# lna-plug.net
KiCad netlist of a schematic drawn in EAGLE
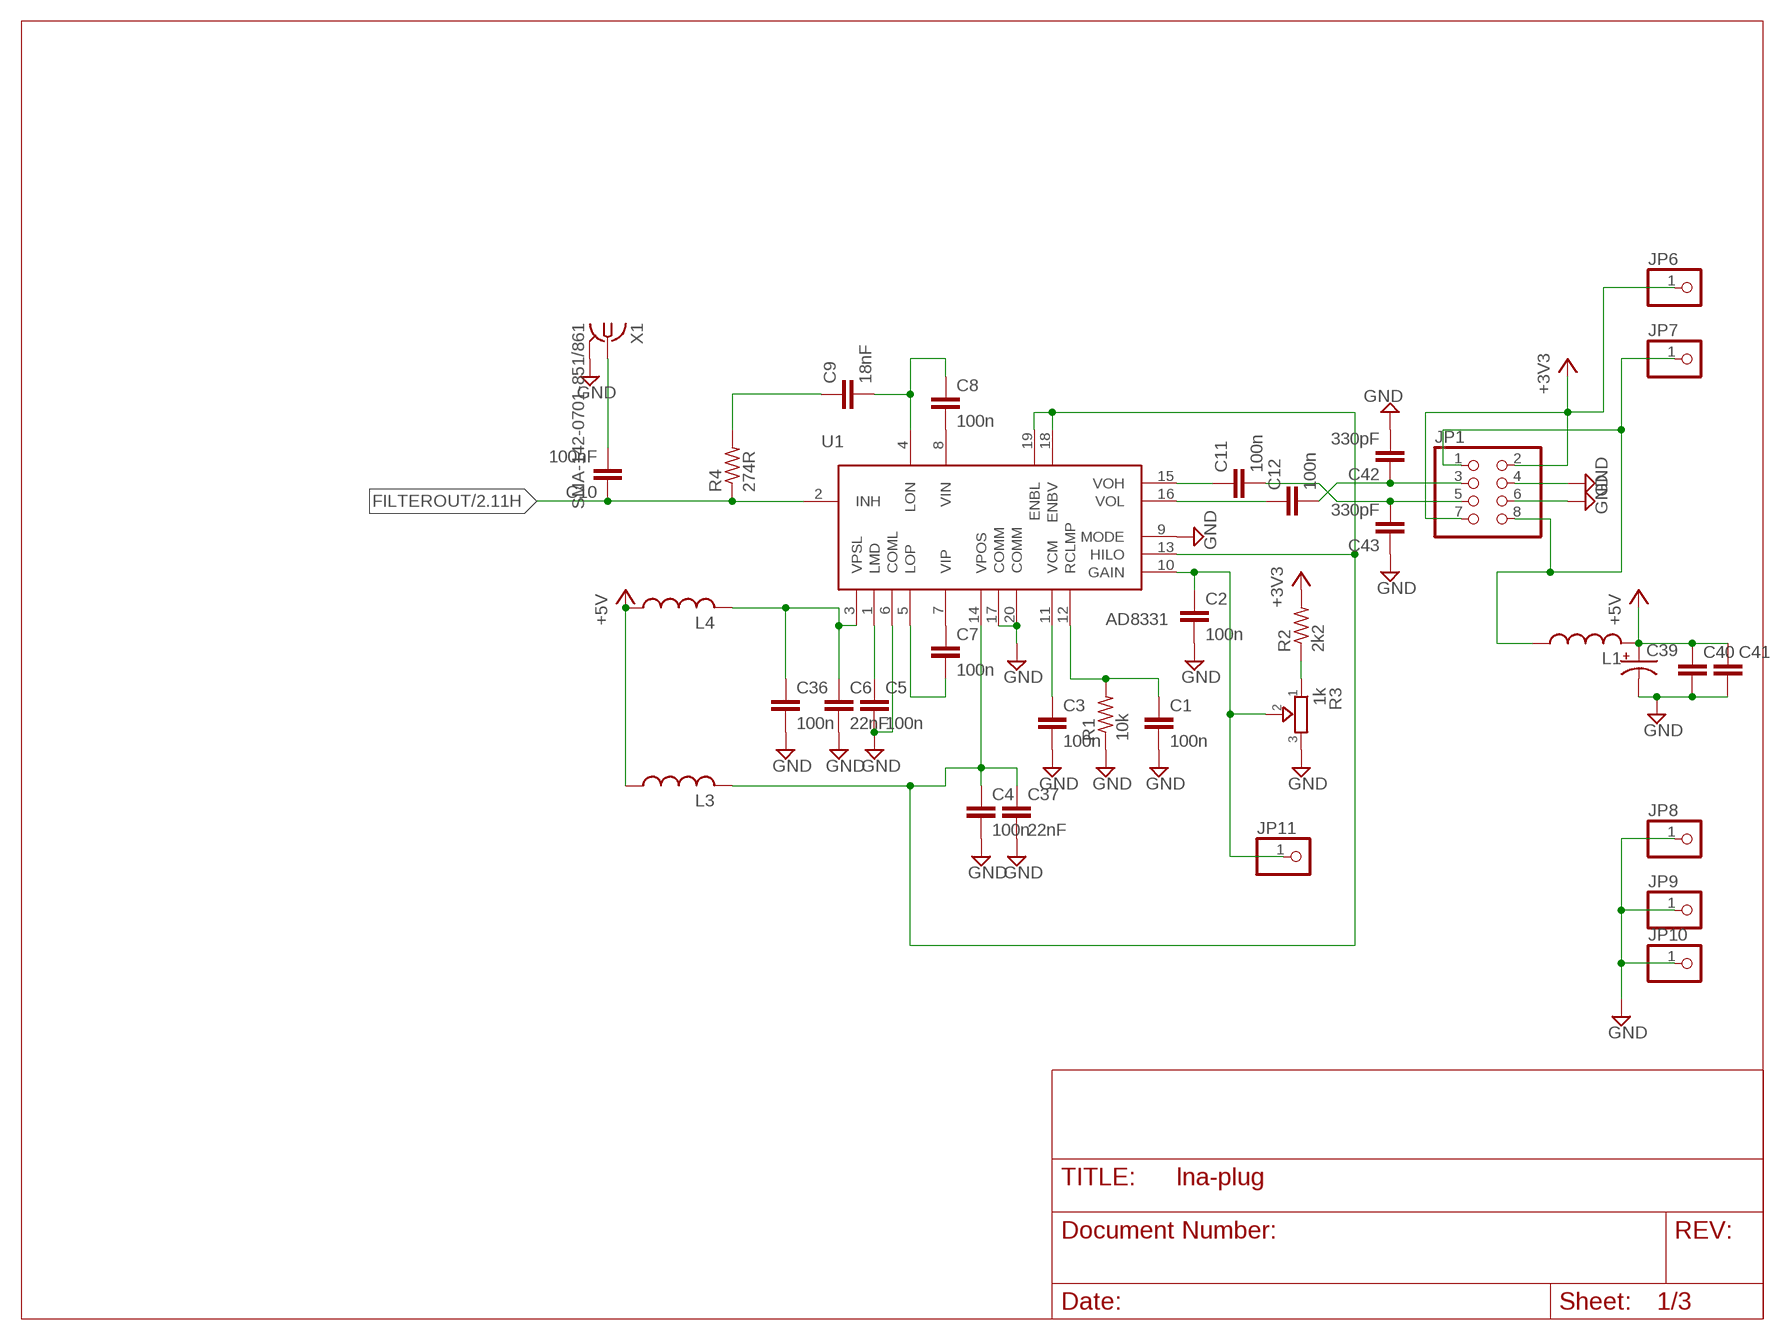
[diagram p0: schematic, sheet 1]
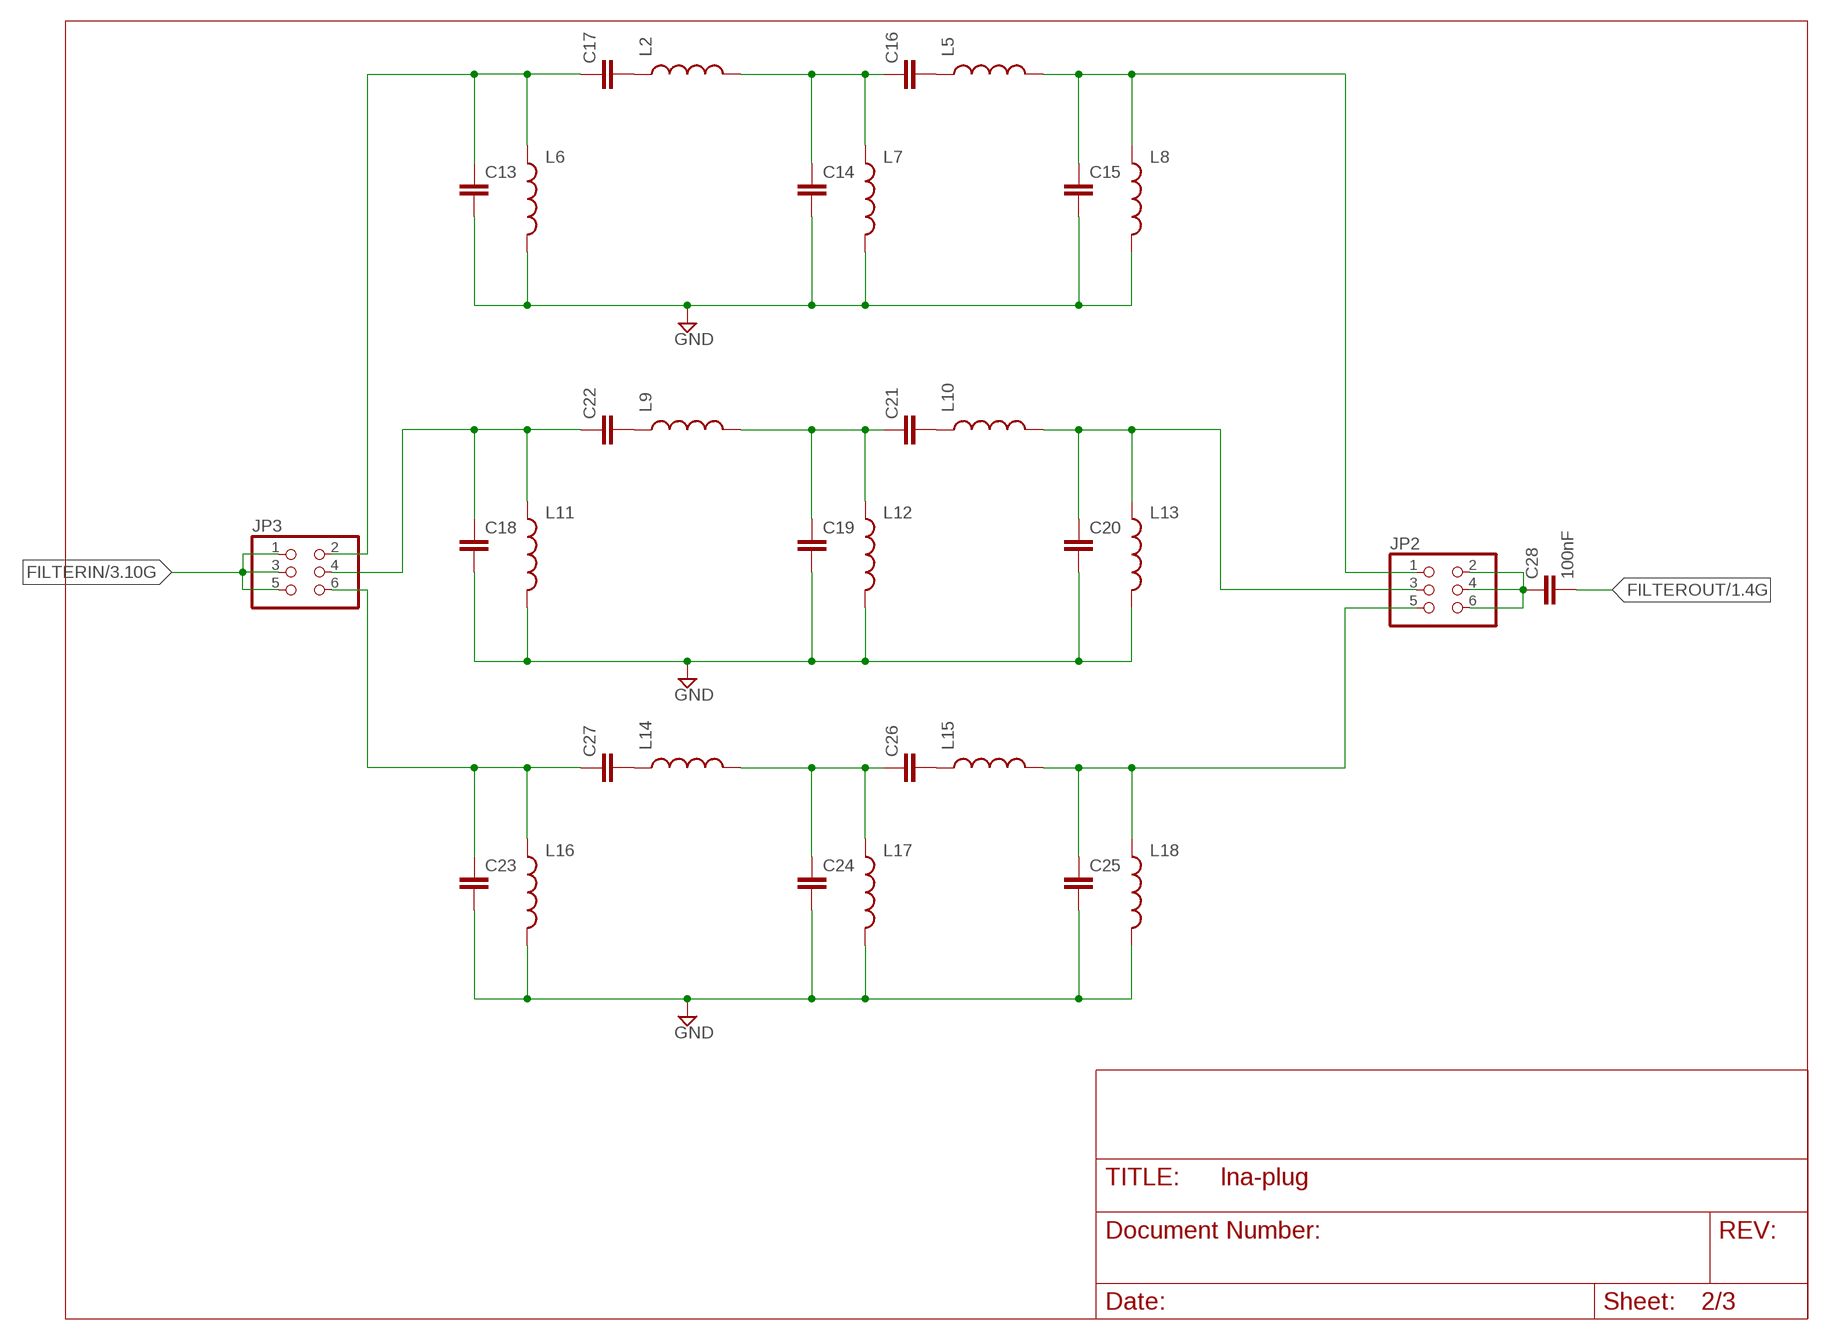
[diagram p1: schematic, sheet 2]
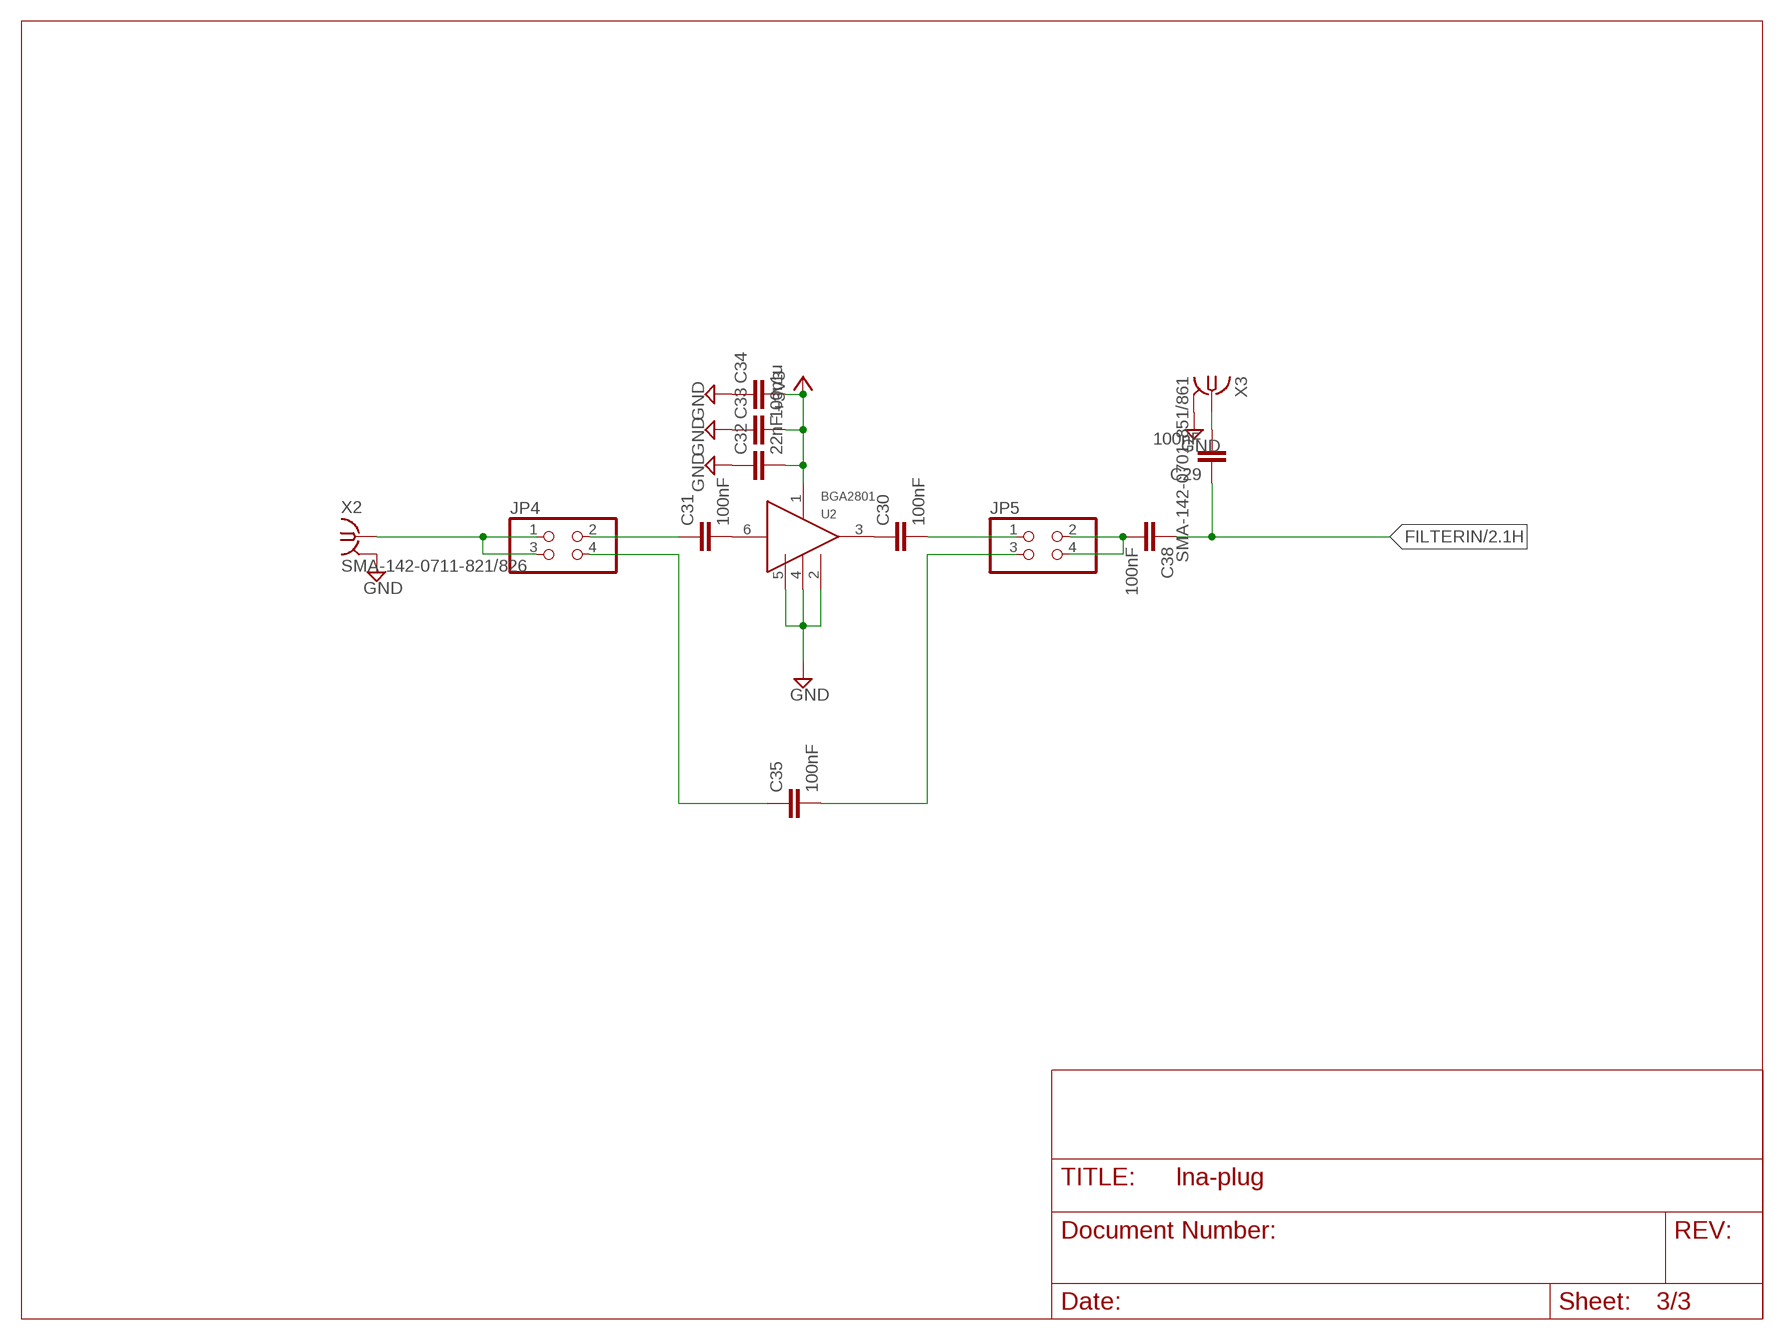
[diagram p2: schematic, sheet 3]

(export (version "E")
  (design (tool "Eeschema 10.0.6"))
  (components
    (comp (ref "C13")
      (value "C-EUC0603")
      (footprint "eagle-import:C0603")
      (libsource (lib "eagle-import") (part "resistor_C-EUC0603"))
    )
    (comp (ref "C14")
      (value "C-EUC0603")
      (footprint "eagle-import:C0603")
      (libsource (lib "eagle-import") (part "resistor_C-EUC0603"))
    )
    (comp (ref "C15")
      (value "C-EUC0603")
      (footprint "eagle-import:C0603")
      (libsource (lib "eagle-import") (part "resistor_C-EUC0603"))
    )
    (comp (ref "C16")
      (value "C-EUC0603")
      (footprint "eagle-import:C0603")
      (libsource (lib "eagle-import") (part "resistor_C-EUC0603"))
    )
    (comp (ref "C17")
      (value "C-EUC0603")
      (footprint "eagle-import:C0603")
      (libsource (lib "eagle-import") (part "resistor_C-EUC0603"))
    )
    (comp (ref "C18")
      (value "C-EUC0603")
      (footprint "eagle-import:C0603")
      (libsource (lib "eagle-import") (part "resistor_C-EUC0603"))
    )
    (comp (ref "C19")
      (value "C-EUC0603")
      (footprint "eagle-import:C0603")
      (libsource (lib "eagle-import") (part "resistor_C-EUC0603"))
    )
    (comp (ref "C20")
      (value "C-EUC0603")
      (footprint "eagle-import:C0603")
      (libsource (lib "eagle-import") (part "resistor_C-EUC0603"))
    )
    (comp (ref "C21")
      (value "C-EUC0603")
      (footprint "eagle-import:C0603")
      (libsource (lib "eagle-import") (part "resistor_C-EUC0603"))
    )
    (comp (ref "C22")
      (value "C-EUC0603")
      (footprint "eagle-import:C0603")
      (libsource (lib "eagle-import") (part "resistor_C-EUC0603"))
    )
    (comp (ref "C23")
      (value "C-EUC0603")
      (footprint "eagle-import:C0603")
      (libsource (lib "eagle-import") (part "resistor_C-EUC0603"))
    )
    (comp (ref "C24")
      (value "C-EUC0603")
      (footprint "eagle-import:C0603")
      (libsource (lib "eagle-import") (part "resistor_C-EUC0603"))
    )
    (comp (ref "C25")
      (value "C-EUC0603")
      (footprint "eagle-import:C0603")
      (libsource (lib "eagle-import") (part "resistor_C-EUC0603"))
    )
    (comp (ref "C26")
      (value "C-EUC0603")
      (footprint "eagle-import:C0603")
      (libsource (lib "eagle-import") (part "resistor_C-EUC0603"))
    )
    (comp (ref "C27")
      (value "C-EUC0603")
      (footprint "eagle-import:C0603")
      (libsource (lib "eagle-import") (part "resistor_C-EUC0603"))
    )
    (comp (ref "C28")
      (value "100nF")
      (footprint "eagle-import:C0603")
      (libsource (lib "eagle-import") (part "resistor_C-EUC0603"))
    )
    (comp (ref "JP2")
      (value "PINHD-2X3")
      (footprint "eagle-import:2X03")
      (libsource (lib "eagle-import") (part "PINHD-2X3"))
    )
    (comp (ref "JP3")
      (value "PINHD-2X3")
      (footprint "eagle-import:2X03")
      (libsource (lib "eagle-import") (part "PINHD-2X3"))
    )
    (comp (ref "L2")
      (value "INDUCTOR0603")
      (footprint "eagle-import:0603")
      (libsource (lib "eagle-import") (part "INDUCTOR0603"))
    )
    (comp (ref "L5")
      (value "INDUCTOR0603")
      (footprint "eagle-import:0603")
      (libsource (lib "eagle-import") (part "INDUCTOR0603"))
    )
    (comp (ref "L6")
      (value "INDUCTOR0603")
      (footprint "eagle-import:0603")
      (libsource (lib "eagle-import") (part "INDUCTOR0603"))
    )
    (comp (ref "L7")
      (value "INDUCTOR0603")
      (footprint "eagle-import:0603")
      (libsource (lib "eagle-import") (part "INDUCTOR0603"))
    )
    (comp (ref "L8")
      (value "INDUCTOR0603")
      (footprint "eagle-import:0603")
      (libsource (lib "eagle-import") (part "INDUCTOR0603"))
    )
    (comp (ref "L9")
      (value "INDUCTOR0603")
      (footprint "eagle-import:0603")
      (libsource (lib "eagle-import") (part "INDUCTOR0603"))
    )
    (comp (ref "L10")
      (value "INDUCTOR0603")
      (footprint "eagle-import:0603")
      (libsource (lib "eagle-import") (part "INDUCTOR0603"))
    )
    (comp (ref "L11")
      (value "INDUCTOR0603")
      (footprint "eagle-import:0603")
      (libsource (lib "eagle-import") (part "INDUCTOR0603"))
    )
    (comp (ref "L12")
      (value "INDUCTOR0603")
      (footprint "eagle-import:0603")
      (libsource (lib "eagle-import") (part "INDUCTOR0603"))
    )
    (comp (ref "L13")
      (value "INDUCTOR0603")
      (footprint "eagle-import:0603")
      (libsource (lib "eagle-import") (part "INDUCTOR0603"))
    )
    (comp (ref "L14")
      (value "INDUCTOR0603")
      (footprint "eagle-import:0603")
      (libsource (lib "eagle-import") (part "INDUCTOR0603"))
    )
    (comp (ref "L15")
      (value "INDUCTOR0603")
      (footprint "eagle-import:0603")
      (libsource (lib "eagle-import") (part "INDUCTOR0603"))
    )
    (comp (ref "L16")
      (value "INDUCTOR0603")
      (footprint "eagle-import:0603")
      (libsource (lib "eagle-import") (part "INDUCTOR0603"))
    )
    (comp (ref "L17")
      (value "INDUCTOR0603")
      (footprint "eagle-import:0603")
      (libsource (lib "eagle-import") (part "INDUCTOR0603"))
    )
    (comp (ref "L18")
      (value "INDUCTOR0603")
      (footprint "eagle-import:0603")
      (libsource (lib "eagle-import") (part "INDUCTOR0603"))
    )
    (comp (ref "C1")
      (value "100n")
      (footprint "eagle-import:C0603")
      (libsource (lib "eagle-import") (part "resistor_C-EUC0603"))
    )
    (comp (ref "C2")
      (value "100n")
      (footprint "eagle-import:C0603")
      (libsource (lib "eagle-import") (part "resistor_C-EUC0603"))
    )
    (comp (ref "C3")
      (value "100n")
      (footprint "eagle-import:C0603")
      (libsource (lib "eagle-import") (part "resistor_C-EUC0603"))
    )
    (comp (ref "C4")
      (value "100n")
      (footprint "eagle-import:C0603")
      (libsource (lib "eagle-import") (part "resistor_C-EUC0603"))
    )
    (comp (ref "C5")
      (value "100n")
      (footprint "eagle-import:C0603")
      (libsource (lib "eagle-import") (part "resistor_C-EUC0603"))
    )
    (comp (ref "C6")
      (value "22nF")
      (footprint "eagle-import:C0603")
      (libsource (lib "eagle-import") (part "resistor_C-EUC0603"))
    )
    (comp (ref "C7")
      (value "100n")
      (footprint "eagle-import:C0603")
      (libsource (lib "eagle-import") (part "resistor_C-EUC0603"))
    )
    (comp (ref "C8")
      (value "100n")
      (footprint "eagle-import:C0603")
      (libsource (lib "eagle-import") (part "resistor_C-EUC0603"))
    )
    (comp (ref "C9")
      (value "18nF")
      (footprint "eagle-import:C0603")
      (libsource (lib "eagle-import") (part "resistor_C-EUC0603"))
    )
    (comp (ref "C10")
      (value "100nF")
      (footprint "eagle-import:C0603")
      (libsource (lib "eagle-import") (part "resistor_C-EUC0603"))
    )
    (comp (ref "C11")
      (value "100n")
      (footprint "eagle-import:C0603")
      (libsource (lib "eagle-import") (part "resistor_C-EUC0603"))
    )
    (comp (ref "C12")
      (value "100n")
      (footprint "eagle-import:C0603")
      (libsource (lib "eagle-import") (part "resistor_C-EUC0603"))
    )
    (comp (ref "C36")
      (value "100n")
      (footprint "eagle-import:C0603")
      (libsource (lib "eagle-import") (part "resistor_C-EUC0603"))
    )
    (comp (ref "C37")
      (value "22nF")
      (footprint "eagle-import:C0603")
      (libsource (lib "eagle-import") (part "resistor_C-EUC0603"))
    )
    (comp (ref "C39")
      (value "CPOL-USSMCC")
      (footprint "eagle-import:SMC_C")
      (libsource (lib "eagle-import") (part "CPOL-USSMCC"))
    )
    (comp (ref "C40")
      (value "C-EUC1206")
      (footprint "eagle-import:C1206")
      (libsource (lib "eagle-import") (part "C-EUC1206"))
    )
    (comp (ref "C41")
      (value "C-EUC0805")
      (footprint "eagle-import:C0805")
      (libsource (lib "eagle-import") (part "C-EUC0805"))
    )
    (comp (ref "C42")
      (value "330pF")
      (footprint "eagle-import:C0603")
      (libsource (lib "eagle-import") (part "resistor_C-EUC0603"))
    )
    (comp (ref "C43")
      (value "330pF")
      (footprint "eagle-import:C0603")
      (libsource (lib "eagle-import") (part "resistor_C-EUC0603"))
    )
    (comp (ref "JP1")
      (value "PINHD-2X4")
      (footprint "eagle-import:2X04")
      (libsource (lib "eagle-import") (part "PINHD-2X4"))
    )
    (comp (ref "JP6")
      (value "PINHD-1X1")
      (footprint "eagle-import:1X01")
      (libsource (lib "eagle-import") (part "PINHD-1X1"))
    )
    (comp (ref "JP7")
      (value "PINHD-1X1")
      (footprint "eagle-import:1X01")
      (libsource (lib "eagle-import") (part "PINHD-1X1"))
    )
    (comp (ref "JP8")
      (value "PINHD-1X1")
      (footprint "eagle-import:1X01")
      (libsource (lib "eagle-import") (part "PINHD-1X1"))
    )
    (comp (ref "JP9")
      (value "PINHD-1X1")
      (footprint "eagle-import:1X01")
      (libsource (lib "eagle-import") (part "PINHD-1X1"))
    )
    (comp (ref "JP10")
      (value "PINHD-1X1")
      (footprint "eagle-import:1X01")
      (libsource (lib "eagle-import") (part "PINHD-1X1"))
    )
    (comp (ref "JP11")
      (value "PINHD-1X1")
      (footprint "eagle-import:1X01")
      (libsource (lib "eagle-import") (part "PINHD-1X1"))
    )
    (comp (ref "L1")
      (value "L-USL2012C")
      (footprint "eagle-import:L2012C")
      (libsource (lib "eagle-import") (part "L-USL2012C"))
    )
    (comp (ref "L3")
      (value "L-USL2012C")
      (footprint "eagle-import:L2012C")
      (libsource (lib "eagle-import") (part "L-USL2012C"))
    )
    (comp (ref "L4")
      (value "L-USL2012C")
      (footprint "eagle-import:L2012C")
      (libsource (lib "eagle-import") (part "L-USL2012C"))
    )
    (comp (ref "R1")
      (value "10k")
      (footprint "eagle-import:R0603")
      (libsource (lib "eagle-import") (part "R-US_R0603"))
    )
    (comp (ref "R2")
      (value "2k2")
      (footprint "eagle-import:R0603")
      (libsource (lib "eagle-import") (part "R-US_R0603"))
    )
    (comp (ref "R3")
      (value "1k")
      (footprint "eagle-import:TRIMMER_3362P")
      (libsource (lib "eagle-import") (part "TRIMMER-3362P"))
    )
    (comp (ref "R4")
      (value "274R")
      (footprint "eagle-import:R0603")
      (libsource (lib "eagle-import") (part "R-US_R0603"))
    )
    (comp (ref "U1")
      (value "AD8331")
      (footprint "eagle-import:QSOP20")
      (libsource (lib "eagle-import") (part "AD8331"))
    )
    (comp (ref "X1")
      (value "SMA-142-0701-851/861")
      (footprint "eagle-import:J502-ND-142-0701-851_861")
      (fields (field (name "MF") "JOHNSON COMPONENTS") (field (name "MPN") "142-0701-851"))
      (libsource (lib "eagle-import") (part "SMA-142-0701-851/861"))
    )
    (comp (ref "C29")
      (value "100nF")
      (footprint "eagle-import:C0603")
      (libsource (lib "eagle-import") (part "resistor_C-EUC0603"))
    )
    (comp (ref "C30")
      (value "100nF")
      (footprint "eagle-import:C0603")
      (libsource (lib "eagle-import") (part "resistor_C-EUC0603"))
    )
    (comp (ref "C31")
      (value "100nF")
      (footprint "eagle-import:C0603")
      (libsource (lib "eagle-import") (part "resistor_C-EUC0603"))
    )
    (comp (ref "C32")
      (value "22nF")
      (footprint "eagle-import:C0603")
      (libsource (lib "eagle-import") (part "resistor_C-EUC0603"))
    )
    (comp (ref "C33")
      (value "100n")
      (footprint "eagle-import:C0603")
      (libsource (lib "eagle-import") (part "resistor_C-EUC0603"))
    )
    (comp (ref "C34")
      (value "1u")
      (footprint "eagle-import:C0603")
      (libsource (lib "eagle-import") (part "resistor_C-EUC0603"))
    )
    (comp (ref "C35")
      (value "100nF")
      (footprint "eagle-import:C0603")
      (libsource (lib "eagle-import") (part "resistor_C-EUC0603"))
    )
    (comp (ref "C38")
      (value "100nF")
      (footprint "eagle-import:C0603")
      (libsource (lib "eagle-import") (part "resistor_C-EUC0603"))
    )
    (comp (ref "JP4")
      (value "PINHD-2X2")
      (footprint "eagle-import:2X02")
      (libsource (lib "eagle-import") (part "PINHD-2X2"))
    )
    (comp (ref "JP5")
      (value "PINHD-2X2")
      (footprint "eagle-import:2X02")
      (libsource (lib "eagle-import") (part "PINHD-2X2"))
    )
    (comp (ref "U2")
      (value "BGA2801")
      (footprint "eagle-import:SOTT323-6")
      (libsource (lib "eagle-import") (part "BGA2801"))
    )
    (comp (ref "X2")
      (value "SMA-142-0711-821/826")
      (footprint "eagle-import:J502-ND-142-0711-821_826")
      (fields (field (name "MF") "JOHNSON COMPONENTS") (field (name "MPN") "142-0711-821"))
      (libsource (lib "eagle-import") (part "SMA-142-0711-821/826"))
    )
    (comp (ref "X3")
      (value "SMA-142-0701-851/861")
      (footprint "eagle-import:J502-ND-142-0701-851_861")
      (fields (field (name "MF") "JOHNSON COMPONENTS") (field (name "MPN") "142-0701-851"))
      (libsource (lib "eagle-import") (part "SMA-142-0701-851/861"))
    )
  )
  (nets
    (net (code "1") (name "+3V3") (class "Default")
      (node (ref "C32") (pin "2") (pinfunction "2_2") (pintype "passive"))
      (node (ref "C33") (pin "2") (pinfunction "2_2") (pintype "passive"))
      (node (ref "C34") (pin "2") (pinfunction "2_2") (pintype "passive"))
      (node (ref "JP1") (pin "2") (pinfunction "2_2") (pintype "passive"))
      (node (ref "JP1") (pin "7") (pinfunction "7_7") (pintype "passive"))
      (node (ref "JP6") (pin "1") (pinfunction "1_1") (pintype "passive"))
      (node (ref "R2") (pin "2") (pinfunction "2_2") (pintype "passive"))
      (node (ref "U2") (pin "1") (pinfunction "VCC_1") (pintype "bidirectional"))
    )
    (net (code "2") (name "+5V") (class "Default")
      (node (ref "C39") (pin "+") (pinfunction "+_+") (pintype "passive"))
      (node (ref "C40") (pin "1") (pinfunction "1_1") (pintype "passive"))
      (node (ref "C41") (pin "1") (pinfunction "1_1") (pintype "passive"))
      (node (ref "L1") (pin "2") (pinfunction "2_2") (pintype "passive"))
      (node (ref "L3") (pin "1") (pinfunction "1_1") (pintype "passive"))
      (node (ref "L4") (pin "1") (pinfunction "1_1") (pintype "passive"))
    )
    (net (code "3") (name "FILTERIN") (class "Default")
      (node (ref "C29") (pin "1") (pinfunction "1_1") (pintype "passive"))
      (node (ref "C38") (pin "1") (pinfunction "1_1") (pintype "passive"))
      (node (ref "JP3") (pin "1") (pinfunction "1_1") (pintype "passive"))
      (node (ref "JP3") (pin "3") (pinfunction "3_3") (pintype "passive"))
      (node (ref "JP3") (pin "5") (pinfunction "5_5") (pintype "passive"))
    )
    (net (code "4") (name "FILTEROUT") (class "Default")
      (node (ref "C10") (pin "1") (pinfunction "1_1") (pintype "passive"))
      (node (ref "C28") (pin "2") (pinfunction "2_2") (pintype "passive"))
      (node (ref "R4") (pin "1") (pinfunction "1_1") (pintype "passive"))
      (node (ref "U1") (pin "2") (pinfunction "INH_2") (pintype "bidirectional"))
    )
    (net (code "5") (name "GND") (class "Default")
      (node (ref "C1") (pin "2") (pinfunction "2_2") (pintype "passive"))
      (node (ref "C13") (pin "2") (pinfunction "2_2") (pintype "passive"))
      (node (ref "C14") (pin "2") (pinfunction "2_2") (pintype "passive"))
      (node (ref "C15") (pin "2") (pinfunction "2_2") (pintype "passive"))
      (node (ref "C18") (pin "2") (pinfunction "2_2") (pintype "passive"))
      (node (ref "C19") (pin "2") (pinfunction "2_2") (pintype "passive"))
      (node (ref "C2") (pin "2") (pinfunction "2_2") (pintype "passive"))
      (node (ref "C20") (pin "2") (pinfunction "2_2") (pintype "passive"))
      (node (ref "C23") (pin "2") (pinfunction "2_2") (pintype "passive"))
      (node (ref "C24") (pin "2") (pinfunction "2_2") (pintype "passive"))
      (node (ref "C25") (pin "2") (pinfunction "2_2") (pintype "passive"))
      (node (ref "C3") (pin "2") (pinfunction "2_2") (pintype "passive"))
      (node (ref "C32") (pin "1") (pinfunction "1_1") (pintype "passive"))
      (node (ref "C33") (pin "1") (pinfunction "1_1") (pintype "passive"))
      (node (ref "C34") (pin "1") (pinfunction "1_1") (pintype "passive"))
      (node (ref "C36") (pin "2") (pinfunction "2_2") (pintype "passive"))
      (node (ref "C37") (pin "2") (pinfunction "2_2") (pintype "passive"))
      (node (ref "C39") (pin "-") (pinfunction "-_-") (pintype "passive"))
      (node (ref "C4") (pin "2") (pinfunction "2_2") (pintype "passive"))
      (node (ref "C40") (pin "2") (pinfunction "2_2") (pintype "passive"))
      (node (ref "C41") (pin "2") (pinfunction "2_2") (pintype "passive"))
      (node (ref "C42") (pin "2") (pinfunction "2_2") (pintype "passive"))
      (node (ref "C43") (pin "1") (pinfunction "1_1") (pintype "passive"))
      (node (ref "C5") (pin "2") (pinfunction "2_2") (pintype "passive"))
      (node (ref "C6") (pin "2") (pinfunction "2_2") (pintype "passive"))
      (node (ref "JP1") (pin "4") (pinfunction "4_4") (pintype "passive"))
      (node (ref "JP1") (pin "6") (pinfunction "6_6") (pintype "passive"))
      (node (ref "JP10") (pin "1") (pinfunction "1_1") (pintype "passive"))
      (node (ref "JP8") (pin "1") (pinfunction "1_1") (pintype "passive"))
      (node (ref "JP9") (pin "1") (pinfunction "1_1") (pintype "passive"))
      (node (ref "L11") (pin "2") (pinfunction "2_2") (pintype "passive"))
      (node (ref "L12") (pin "2") (pinfunction "2_2") (pintype "passive"))
      (node (ref "L13") (pin "2") (pinfunction "2_2") (pintype "passive"))
      (node (ref "L16") (pin "2") (pinfunction "2_2") (pintype "passive"))
      (node (ref "L17") (pin "2") (pinfunction "2_2") (pintype "passive"))
      (node (ref "L18") (pin "2") (pinfunction "2_2") (pintype "passive"))
      (node (ref "L6") (pin "2") (pinfunction "2_2") (pintype "passive"))
      (node (ref "L7") (pin "2") (pinfunction "2_2") (pintype "passive"))
      (node (ref "L8") (pin "2") (pinfunction "2_2") (pintype "passive"))
      (node (ref "R1") (pin "1") (pinfunction "1_1") (pintype "passive"))
      (node (ref "R3") (pin "3") (pinfunction "3_3") (pintype "passive"))
      (node (ref "U1") (pin "17") (pinfunction "COMM_17") (pintype "bidirectional"))
      (node (ref "U1") (pin "20") (pinfunction "COMM_20") (pintype "bidirectional"))
      (node (ref "U1") (pin "6") (pinfunction "COML_6") (pintype "bidirectional"))
      (node (ref "U1") (pin "9") (pinfunction "MODE_9") (pintype "bidirectional"))
      (node (ref "U2") (pin "2") (pinfunction "GND_2") (pintype "bidirectional"))
      (node (ref "U2") (pin "4") (pinfunction "GND_4") (pintype "bidirectional"))
      (node (ref "U2") (pin "5") (pinfunction "GND_5") (pintype "bidirectional"))
      (node (ref "X1") (pin "G@1") (pinfunction "2_G@1") (pintype "passive"))
      (node (ref "X1") (pin "G@2") (pinfunction "2_G@2") (pintype "passive"))
      (node (ref "X1") (pin "G@3") (pinfunction "2_G@3") (pintype "passive"))
      (node (ref "X1") (pin "G@4") (pinfunction "2_G@4") (pintype "passive"))
      (node (ref "X2") (pin "G@1") (pinfunction "2_G@1") (pintype "passive"))
      (node (ref "X2") (pin "G@2") (pinfunction "2_G@2") (pintype "passive"))
      (node (ref "X2") (pin "G@3") (pinfunction "2_G@3") (pintype "passive"))
      (node (ref "X2") (pin "G@4") (pinfunction "2_G@4") (pintype "passive"))
      (node (ref "X3") (pin "G@1") (pinfunction "2_G@1") (pintype "passive"))
      (node (ref "X3") (pin "G@2") (pinfunction "2_G@2") (pintype "passive"))
      (node (ref "X3") (pin "G@3") (pinfunction "2_G@3") (pintype "passive"))
      (node (ref "X3") (pin "G@4") (pinfunction "2_G@4") (pintype "passive"))
    )
    (net (code "6") (name "Net-(C9-Pad1)") (class "Default")
      (node (ref "C9") (pin "1") (pinfunction "1_1") (pintype "passive"))
      (node (ref "R4") (pin "2") (pinfunction "2_2") (pintype "passive"))
    )
    (net (code "7") (name "Net-(C10-Pad2)") (class "Default")
      (node (ref "C10") (pin "2") (pinfunction "2_2") (pintype "passive"))
      (node (ref "X1") (pin "1") (pinfunction "1_1") (pintype "passive"))
    )
    (net (code "8") (name "Net-(C11-Pad2)") (class "Default")
      (node (ref "C11") (pin "2") (pinfunction "2_2") (pintype "passive"))
      (node (ref "C43") (pin "2") (pinfunction "2_2") (pintype "passive"))
      (node (ref "JP1") (pin "5") (pinfunction "5_5") (pintype "passive"))
    )
    (net (code "9") (name "Net-(C12-Pad2)") (class "Default")
      (node (ref "C12") (pin "2") (pinfunction "2_2") (pintype "passive"))
      (node (ref "C42") (pin "1") (pinfunction "1_1") (pintype "passive"))
      (node (ref "JP1") (pin "3") (pinfunction "3_3") (pintype "passive"))
    )
    (net (code "10") (name "Net-(C13-Pad1)") (class "Default")
      (node (ref "C13") (pin "1") (pinfunction "1_1") (pintype "passive"))
      (node (ref "C17") (pin "1") (pinfunction "1_1") (pintype "passive"))
      (node (ref "JP3") (pin "2") (pinfunction "2_2") (pintype "passive"))
      (node (ref "L6") (pin "1") (pinfunction "1_1") (pintype "passive"))
    )
    (net (code "11") (name "Net-(C14-Pad1)") (class "Default")
      (node (ref "C14") (pin "1") (pinfunction "1_1") (pintype "passive"))
      (node (ref "C16") (pin "1") (pinfunction "1_1") (pintype "passive"))
      (node (ref "L2") (pin "2") (pinfunction "2_2") (pintype "passive"))
      (node (ref "L7") (pin "1") (pinfunction "1_1") (pintype "passive"))
    )
    (net (code "12") (name "Net-(C15-Pad1)") (class "Default")
      (node (ref "C15") (pin "1") (pinfunction "1_1") (pintype "passive"))
      (node (ref "JP2") (pin "1") (pinfunction "1_1") (pintype "passive"))
      (node (ref "L5") (pin "2") (pinfunction "2_2") (pintype "passive"))
      (node (ref "L8") (pin "1") (pinfunction "1_1") (pintype "passive"))
    )
    (net (code "13") (name "Net-(C16-Pad2)") (class "Default")
      (node (ref "C16") (pin "2") (pinfunction "2_2") (pintype "passive"))
      (node (ref "L5") (pin "1") (pinfunction "1_1") (pintype "passive"))
    )
    (net (code "14") (name "Net-(C17-Pad2)") (class "Default")
      (node (ref "C17") (pin "2") (pinfunction "2_2") (pintype "passive"))
      (node (ref "L2") (pin "1") (pinfunction "1_1") (pintype "passive"))
    )
    (net (code "15") (name "Net-(C18-Pad1)") (class "Default")
      (node (ref "C18") (pin "1") (pinfunction "1_1") (pintype "passive"))
      (node (ref "C22") (pin "1") (pinfunction "1_1") (pintype "passive"))
      (node (ref "JP3") (pin "4") (pinfunction "4_4") (pintype "passive"))
      (node (ref "L11") (pin "1") (pinfunction "1_1") (pintype "passive"))
    )
    (net (code "16") (name "Net-(C19-Pad1)") (class "Default")
      (node (ref "C19") (pin "1") (pinfunction "1_1") (pintype "passive"))
      (node (ref "C21") (pin "1") (pinfunction "1_1") (pintype "passive"))
      (node (ref "L12") (pin "1") (pinfunction "1_1") (pintype "passive"))
      (node (ref "L9") (pin "2") (pinfunction "2_2") (pintype "passive"))
    )
    (net (code "17") (name "Net-(C20-Pad1)") (class "Default")
      (node (ref "C20") (pin "1") (pinfunction "1_1") (pintype "passive"))
      (node (ref "JP2") (pin "3") (pinfunction "3_3") (pintype "passive"))
      (node (ref "L10") (pin "2") (pinfunction "2_2") (pintype "passive"))
      (node (ref "L13") (pin "1") (pinfunction "1_1") (pintype "passive"))
    )
    (net (code "18") (name "Net-(C21-Pad2)") (class "Default")
      (node (ref "C21") (pin "2") (pinfunction "2_2") (pintype "passive"))
      (node (ref "L10") (pin "1") (pinfunction "1_1") (pintype "passive"))
    )
    (net (code "19") (name "Net-(C22-Pad2)") (class "Default")
      (node (ref "C22") (pin "2") (pinfunction "2_2") (pintype "passive"))
      (node (ref "L9") (pin "1") (pinfunction "1_1") (pintype "passive"))
    )
    (net (code "20") (name "Net-(C23-Pad1)") (class "Default")
      (node (ref "C23") (pin "1") (pinfunction "1_1") (pintype "passive"))
      (node (ref "C27") (pin "1") (pinfunction "1_1") (pintype "passive"))
      (node (ref "JP3") (pin "6") (pinfunction "6_6") (pintype "passive"))
      (node (ref "L16") (pin "1") (pinfunction "1_1") (pintype "passive"))
    )
    (net (code "21") (name "Net-(C24-Pad1)") (class "Default")
      (node (ref "C24") (pin "1") (pinfunction "1_1") (pintype "passive"))
      (node (ref "C26") (pin "1") (pinfunction "1_1") (pintype "passive"))
      (node (ref "L14") (pin "2") (pinfunction "2_2") (pintype "passive"))
      (node (ref "L17") (pin "1") (pinfunction "1_1") (pintype "passive"))
    )
    (net (code "22") (name "Net-(C25-Pad1)") (class "Default")
      (node (ref "C25") (pin "1") (pinfunction "1_1") (pintype "passive"))
      (node (ref "JP2") (pin "5") (pinfunction "5_5") (pintype "passive"))
      (node (ref "L15") (pin "2") (pinfunction "2_2") (pintype "passive"))
      (node (ref "L18") (pin "1") (pinfunction "1_1") (pintype "passive"))
    )
    (net (code "23") (name "Net-(C26-Pad2)") (class "Default")
      (node (ref "C26") (pin "2") (pinfunction "2_2") (pintype "passive"))
      (node (ref "L15") (pin "1") (pinfunction "1_1") (pintype "passive"))
    )
    (net (code "24") (name "Net-(C27-Pad2)") (class "Default")
      (node (ref "C27") (pin "2") (pinfunction "2_2") (pintype "passive"))
      (node (ref "L14") (pin "1") (pinfunction "1_1") (pintype "passive"))
    )
    (net (code "25") (name "Net-(C28-Pad1)") (class "Default")
      (node (ref "C28") (pin "1") (pinfunction "1_1") (pintype "passive"))
      (node (ref "JP2") (pin "2") (pinfunction "2_2") (pintype "passive"))
      (node (ref "JP2") (pin "4") (pinfunction "4_4") (pintype "passive"))
      (node (ref "JP2") (pin "6") (pinfunction "6_6") (pintype "passive"))
    )
    (net (code "26") (name "Net-(C29-Pad2)") (class "Default")
      (node (ref "C29") (pin "2") (pinfunction "2_2") (pintype "passive"))
      (node (ref "X3") (pin "1") (pinfunction "1_1") (pintype "passive"))
    )
    (net (code "27") (name "Net-(C30-Pad2)") (class "Default")
      (node (ref "C30") (pin "2") (pinfunction "2_2") (pintype "passive"))
      (node (ref "JP5") (pin "1") (pinfunction "1_1") (pintype "passive"))
    )
    (net (code "28") (name "Net-(C31-Pad1)") (class "Default")
      (node (ref "C31") (pin "1") (pinfunction "1_1") (pintype "passive"))
      (node (ref "JP4") (pin "2") (pinfunction "2_2") (pintype "passive"))
    )
    (net (code "29") (name "Net-(C35-Pad1)") (class "Default")
      (node (ref "C35") (pin "1") (pinfunction "1_1") (pintype "passive"))
      (node (ref "JP4") (pin "4") (pinfunction "4_4") (pintype "passive"))
    )
    (net (code "30") (name "Net-(C35-Pad2)") (class "Default")
      (node (ref "C35") (pin "2") (pinfunction "2_2") (pintype "passive"))
      (node (ref "JP5") (pin "3") (pinfunction "3_3") (pintype "passive"))
    )
    (net (code "31") (name "Net-(C38-Pad2)") (class "Default")
      (node (ref "C38") (pin "2") (pinfunction "2_2") (pintype "passive"))
      (node (ref "JP5") (pin "2") (pinfunction "2_2") (pintype "passive"))
      (node (ref "JP5") (pin "4") (pinfunction "4_4") (pintype "passive"))
    )
    (net (code "32") (name "Net-(JP1-Pad1)") (class "Default")
      (node (ref "JP1") (pin "1") (pinfunction "1_1") (pintype "passive"))
      (node (ref "JP1") (pin "8") (pinfunction "8_8") (pintype "passive"))
      (node (ref "JP7") (pin "1") (pinfunction "1_1") (pintype "passive"))
      (node (ref "L1") (pin "1") (pinfunction "1_1") (pintype "passive"))
    )
    (net (code "33") (name "Net-(JP4-Pad1)") (class "Default")
      (node (ref "JP4") (pin "1") (pinfunction "1_1") (pintype "passive"))
      (node (ref "JP4") (pin "3") (pinfunction "3_3") (pintype "passive"))
      (node (ref "X2") (pin "1") (pinfunction "1_1") (pintype "passive"))
    )
    (net (code "34") (name "Net-(R2-Pad1)") (class "Default")
      (node (ref "R2") (pin "1") (pinfunction "1_1") (pintype "passive"))
      (node (ref "R3") (pin "1") (pinfunction "1_1") (pintype "passive"))
    )
    (net (code "35") (name "Net-(U1-ENBL)") (class "Default")
      (node (ref "C37") (pin "1") (pinfunction "1_1") (pintype "passive"))
      (node (ref "C4") (pin "1") (pinfunction "1_1") (pintype "passive"))
      (node (ref "L3") (pin "2") (pinfunction "2_2") (pintype "passive"))
      (node (ref "U1") (pin "13") (pinfunction "HILO_13") (pintype "bidirectional"))
      (node (ref "U1") (pin "14") (pinfunction "VPOS_14") (pintype "bidirectional"))
      (node (ref "U1") (pin "18") (pinfunction "ENBV_18") (pintype "bidirectional"))
      (node (ref "U1") (pin "19") (pinfunction "ENBL_19") (pintype "bidirectional"))
    )
    (net (code "36") (name "Net-(U1-GAIN)") (class "Default")
      (node (ref "C2") (pin "1") (pinfunction "1_1") (pintype "passive"))
      (node (ref "JP11") (pin "1") (pinfunction "1_1") (pintype "passive"))
      (node (ref "R3") (pin "2") (pinfunction "2_2") (pintype "passive"))
      (node (ref "U1") (pin "10") (pinfunction "GAIN_10") (pintype "bidirectional"))
    )
    (net (code "37") (name "Net-(U1-LMD)") (class "Default")
      (node (ref "C5") (pin "1") (pinfunction "1_1") (pintype "passive"))
      (node (ref "U1") (pin "1") (pinfunction "LMD_1") (pintype "bidirectional"))
    )
    (net (code "38") (name "Net-(U1-LON)") (class "Default")
      (node (ref "C8") (pin "1") (pinfunction "1_1") (pintype "passive"))
      (node (ref "C9") (pin "2") (pinfunction "2_2") (pintype "passive"))
      (node (ref "U1") (pin "4") (pinfunction "LON_4") (pintype "bidirectional"))
    )
    (net (code "39") (name "Net-(U1-LOP)") (class "Default")
      (node (ref "C7") (pin "2") (pinfunction "2_2") (pintype "passive"))
      (node (ref "U1") (pin "5") (pinfunction "LOP_5") (pintype "bidirectional"))
    )
    (net (code "40") (name "Net-(U1-RCLMP)") (class "Default")
      (node (ref "C1") (pin "1") (pinfunction "1_1") (pintype "passive"))
      (node (ref "R1") (pin "2") (pinfunction "2_2") (pintype "passive"))
      (node (ref "U1") (pin "12") (pinfunction "RCLMP_12") (pintype "bidirectional"))
    )
    (net (code "41") (name "Net-(U1-VCM)") (class "Default")
      (node (ref "C3") (pin "1") (pinfunction "1_1") (pintype "passive"))
      (node (ref "U1") (pin "11") (pinfunction "VCM_11") (pintype "bidirectional"))
    )
    (net (code "42") (name "Net-(U1-VIN)") (class "Default")
      (node (ref "C8") (pin "2") (pinfunction "2_2") (pintype "passive"))
      (node (ref "U1") (pin "8") (pinfunction "VIN_8") (pintype "bidirectional"))
    )
    (net (code "43") (name "Net-(U1-VIP)") (class "Default")
      (node (ref "C7") (pin "1") (pinfunction "1_1") (pintype "passive"))
      (node (ref "U1") (pin "7") (pinfunction "VIP_7") (pintype "bidirectional"))
    )
    (net (code "44") (name "Net-(U1-VOH)") (class "Default")
      (node (ref "C11") (pin "1") (pinfunction "1_1") (pintype "passive"))
      (node (ref "U1") (pin "15") (pinfunction "VOH_15") (pintype "bidirectional"))
    )
    (net (code "45") (name "Net-(U1-VOL)") (class "Default")
      (node (ref "C12") (pin "1") (pinfunction "1_1") (pintype "passive"))
      (node (ref "U1") (pin "16") (pinfunction "VOL_16") (pintype "bidirectional"))
    )
    (net (code "46") (name "Net-(U1-VPSL)") (class "Default")
      (node (ref "C36") (pin "1") (pinfunction "1_1") (pintype "passive"))
      (node (ref "C6") (pin "1") (pinfunction "1_1") (pintype "passive"))
      (node (ref "L4") (pin "2") (pinfunction "2_2") (pintype "passive"))
      (node (ref "U1") (pin "3") (pinfunction "VPSL_3") (pintype "bidirectional"))
    )
    (net (code "47") (name "Net-(U2-IN)") (class "Default")
      (node (ref "C31") (pin "2") (pinfunction "2_2") (pintype "passive"))
      (node (ref "U2") (pin "6") (pinfunction "IN_6") (pintype "bidirectional"))
    )
    (net (code "48") (name "Net-(U2-OUT)") (class "Default")
      (node (ref "C30") (pin "1") (pinfunction "1_1") (pintype "passive"))
      (node (ref "U2") (pin "3") (pinfunction "OUT_3") (pintype "bidirectional"))
    )
  )
)
